# MoteinoR5USB.net
KiCad netlist of a schematic drawn in EAGLE
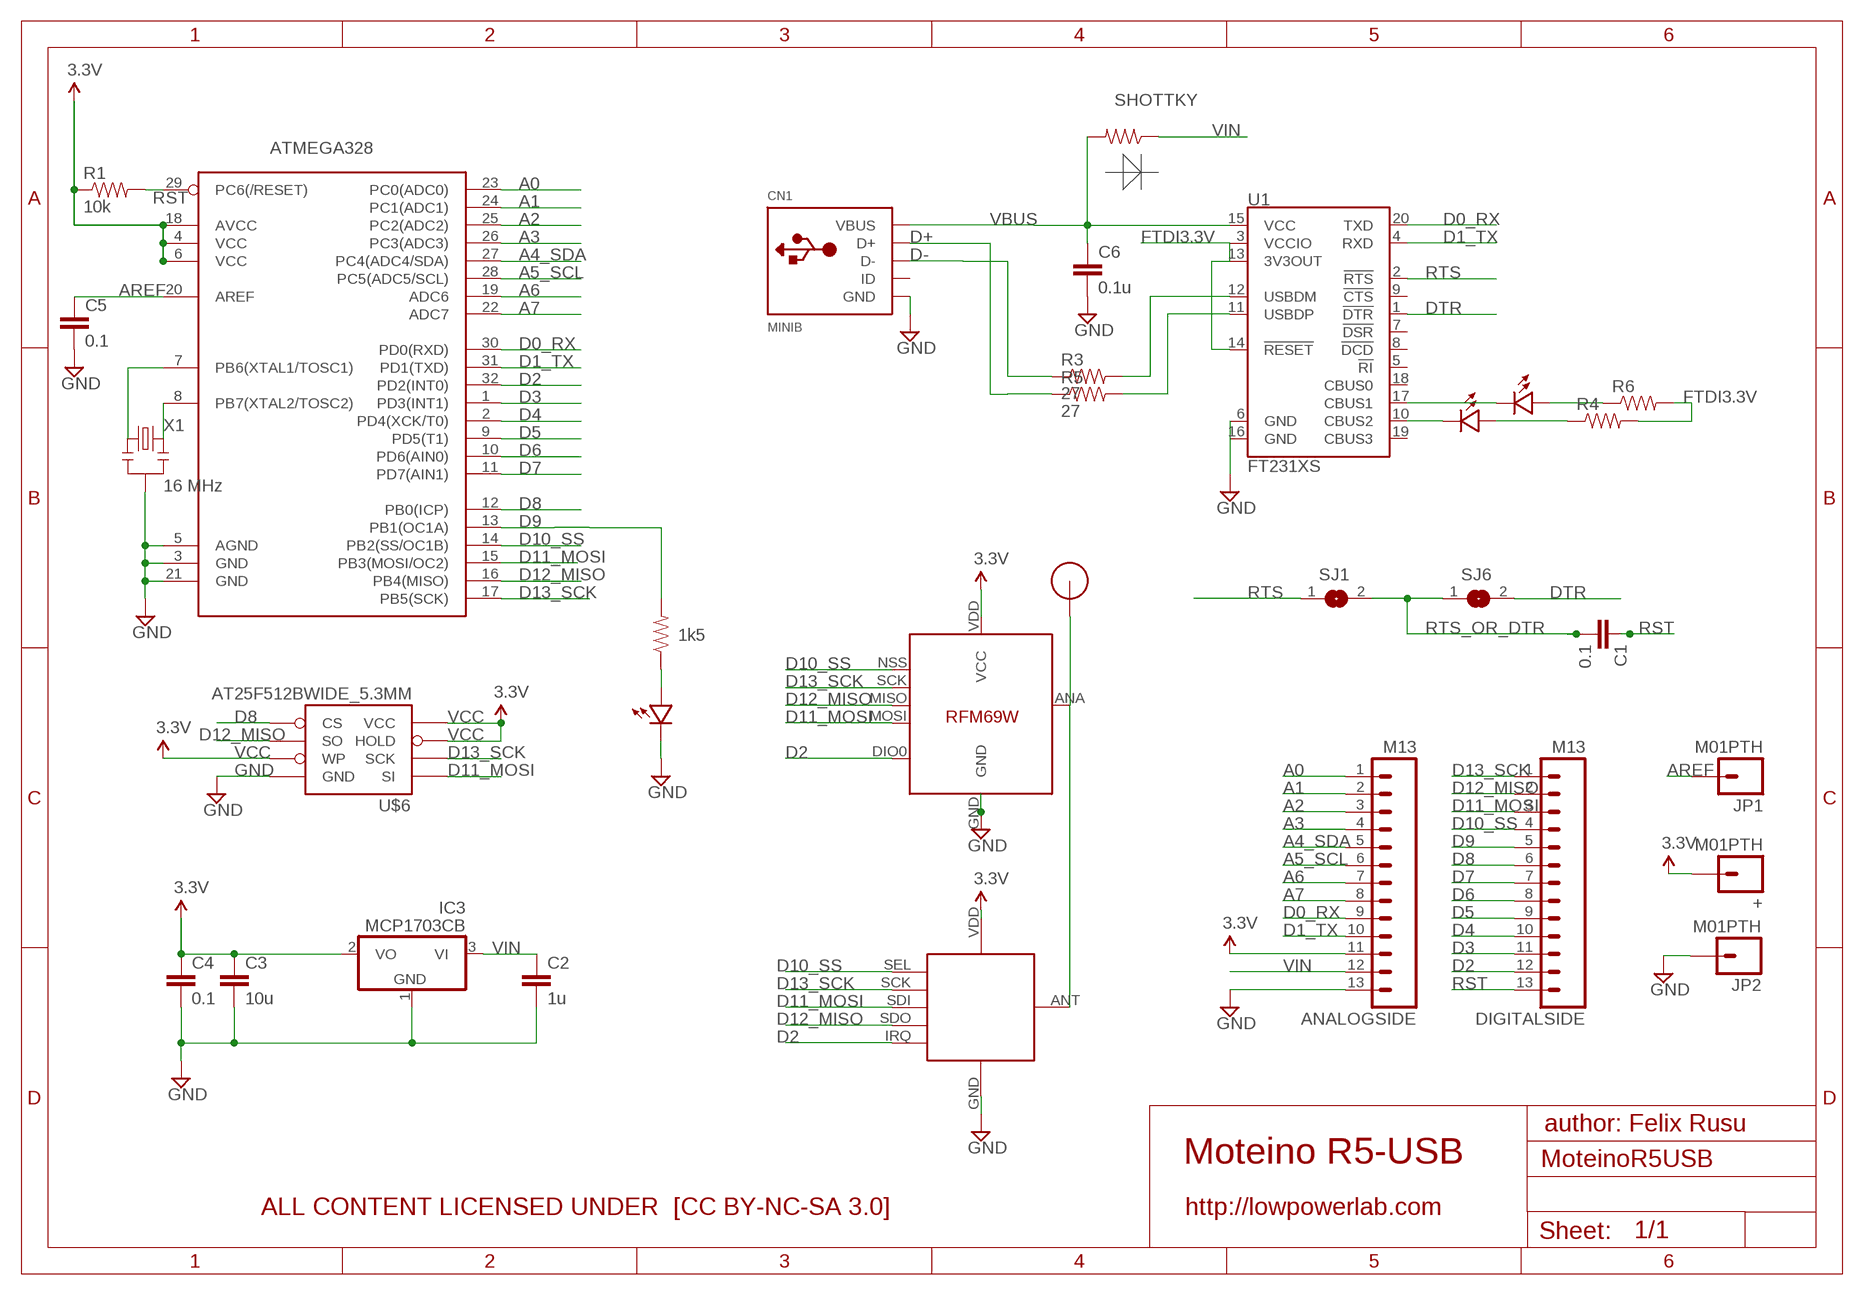
[diagram p0: schematic, sheet 1]

(export (version "E")
  (design (tool "Eeschema 10.0.6"))
  (components
    (comp (ref "+")
      (value "M01PTH")
      (footprint "eagle-import:1X01")
      (libsource (lib "eagle-import") (part "M01PTH"))
    )
    (comp (ref "ANALOGSIDE")
      (value "M13")
      (footprint "eagle-import:1X13")
      (libsource (lib "eagle-import") (part "M13"))
    )
    (comp (ref "ATMEGA328")
      (value "ATMega-328")
      (footprint "eagle-import:TQFP32-08")
      (libsource (lib "eagle-import") (part "ATMEGA168/328TQFP32"))
    )
    (comp (ref "C1")
      (value "0.1")
      (footprint "eagle-import:0603-CAP")
      (libsource (lib "eagle-import") (part "CAP0603-CAP"))
    )
    (comp (ref "C2")
      (value "1u")
      (footprint "eagle-import:0603-CAP")
      (libsource (lib "eagle-import") (part "CAP0603-CAP"))
    )
    (comp (ref "C3")
      (value "10u")
      (footprint "eagle-import:0805-CAP")
      (libsource (lib "eagle-import") (part "CAP0805-CAP"))
    )
    (comp (ref "C4")
      (value "0.1")
      (footprint "eagle-import:0603-CAP")
      (libsource (lib "eagle-import") (part "CAP0603-CAP"))
    )
    (comp (ref "C5")
      (value "0.1")
      (footprint "eagle-import:0603-CAP")
      (libsource (lib "eagle-import") (part "CAP0603-CAP"))
    )
    (comp (ref "C6")
      (value "0.1u")
      (footprint "eagle-import:0603-CAP")
      (libsource (lib "eagle-import") (part "CAP0603-CAP"))
    )
    (comp (ref "CN1")
      (value "MINIB")
      (footprint "eagle-import:USB-MINIB")
      (libsource (lib "eagle-import") (part "USBMINIB"))
    )
    (comp (ref "D")
      (value "SHOTTKY")
      (footprint "eagle-import:0603-RES")
      (libsource (lib "eagle-import") (part "RESISTOR0603-RES"))
    )
    (comp (ref "DIGITALSIDE")
      (value "M13")
      (footprint "eagle-import:1X13")
      (libsource (lib "eagle-import") (part "M13"))
    )
    (comp (ref "IC3")
      (value "MCP1703CB")
      (footprint "eagle-import:SOT23")
      (libsource (lib "eagle-import") (part "MCP1703CB"))
    )
    (comp (ref "JP1")
      (value "M01PTH")
      (footprint "eagle-import:1X01")
      (libsource (lib "eagle-import") (part "M01PTH"))
    )
    (comp (ref "JP2")
      (value "M01PTH")
      (footprint "eagle-import:1X01")
      (libsource (lib "eagle-import") (part "M01PTH"))
    )
    (comp (ref "R1")
      (value "10k")
      (footprint "eagle-import:0603-RES")
      (libsource (lib "eagle-import") (part "RESISTOR0603-RES"))
    )
    (comp (ref "R2")
      (value "1k5")
      (footprint "eagle-import:0603-RES")
      (libsource (lib "eagle-import") (part "RESISTOR0603-RES"))
    )
    (comp (ref "R3")
      (value "27")
      (footprint "eagle-import:0603-RES")
      (libsource (lib "eagle-import") (part "RESISTOR0603-RES"))
    )
    (comp (ref "R4")
      (value "RESISTOR0603-RES")
      (footprint "eagle-import:0603-RES")
      (libsource (lib "eagle-import") (part "RESISTOR0603-RES"))
    )
    (comp (ref "R5")
      (value "27")
      (footprint "eagle-import:0603-RES")
      (libsource (lib "eagle-import") (part "RESISTOR0603-RES"))
    )
    (comp (ref "R6")
      (value "RESISTOR0603-RES")
      (footprint "eagle-import:0603-RES")
      (libsource (lib "eagle-import") (part "RESISTOR0603-RES"))
    )
    (comp (ref "RFM12B")
      (value "RFM12B_MINPADS")
      (footprint "eagle-import:RFM12B-MINPADS")
      (libsource (lib "eagle-import") (part "RFM12B_MINPADS"))
    )
    (comp (ref "SJ1")
      (value "JUMPER")
      (footprint "eagle-import:SJW")
      (libsource (lib "eagle-import") (part "JUMPER"))
    )
    (comp (ref "SJ6")
      (value "JUMPER")
      (footprint "eagle-import:SJW")
      (libsource (lib "eagle-import") (part "JUMPER"))
    )
    (comp (ref "U$1")
      (value "RFM12B_ANTENNA")
      (footprint "eagle-import:RFM12B-ANTENNA")
      (libsource (lib "eagle-import") (part "RFM12B_ANTENNA"))
    )
    (comp (ref "U$2")
      (value "LED0603")
      (footprint "eagle-import:0603-LED")
      (libsource (lib "eagle-import") (part "LED0603"))
    )
    (comp (ref "U$4")
      (value "LED0603")
      (footprint "eagle-import:0603-LED")
      (libsource (lib "eagle-import") (part "LED0603"))
    )
    (comp (ref "U$5")
      (value "RFM69")
      (footprint "eagle-import:RFM69W-MINPADS")
      (libsource (lib "eagle-import") (part "RFM69"))
    )
    (comp (ref "U$6")
      (value "AT25F512BWIDE_5.3MM")
      (footprint "eagle-import:SO08WIDE")
      (libsource (lib "eagle-import") (part "AT25F512BWIDE_5.3MM"))
    )
    (comp (ref "U$7")
      (value "LED0603")
      (footprint "eagle-import:0603-LED")
      (libsource (lib "eagle-import") (part "LED0603"))
    )
    (comp (ref "U1")
      (value "FT231XS")
      (footprint "eagle-import:SSOP20_L")
      (libsource (lib "eagle-import") (part "FT231XS"))
    )
    (comp (ref "X1")
      (value "16 MHz")
      (footprint "eagle-import:RESONATOR-SMD")
      (libsource (lib "eagle-import") (part "RESONATORSMD"))
    )
  )
  (nets
    (net (code "1") (name "/A0") (class "Default")
      (node (ref "ANALOGSIDE") (pin "1") (pinfunction "1_1") (pintype "passive"))
      (node (ref "ATMEGA328") (pin "23") (pinfunction "PC0(ADC0)_23") (pintype "bidirectional"))
    )
    (net (code "2") (name "/A1") (class "Default")
      (node (ref "ANALOGSIDE") (pin "2") (pinfunction "2_2") (pintype "passive"))
      (node (ref "ATMEGA328") (pin "24") (pinfunction "PC1(ADC1)_24") (pintype "bidirectional"))
    )
    (net (code "3") (name "/A2") (class "Default")
      (node (ref "ANALOGSIDE") (pin "3") (pinfunction "3_3") (pintype "passive"))
      (node (ref "ATMEGA328") (pin "25") (pinfunction "PC2(ADC2)_25") (pintype "bidirectional"))
    )
    (net (code "4") (name "/A3") (class "Default")
      (node (ref "ANALOGSIDE") (pin "4") (pinfunction "4_4") (pintype "passive"))
      (node (ref "ATMEGA328") (pin "26") (pinfunction "PC3(ADC3)_26") (pintype "bidirectional"))
    )
    (net (code "5") (name "/A4_SDA") (class "Default")
      (node (ref "ANALOGSIDE") (pin "5") (pinfunction "5_5") (pintype "passive"))
      (node (ref "ATMEGA328") (pin "27") (pinfunction "PC4(ADC4/SDA)_27") (pintype "bidirectional"))
    )
    (net (code "6") (name "/A5_SCL") (class "Default")
      (node (ref "ANALOGSIDE") (pin "6") (pinfunction "6_6") (pintype "passive"))
      (node (ref "ATMEGA328") (pin "28") (pinfunction "PC5(ADC5/SCL)_28") (pintype "bidirectional"))
    )
    (net (code "7") (name "/A6") (class "Default")
      (node (ref "ANALOGSIDE") (pin "7") (pinfunction "7_7") (pintype "passive"))
      (node (ref "ATMEGA328") (pin "19") (pinfunction "ADC6_19") (pintype "bidirectional"))
    )
    (net (code "8") (name "/A7") (class "Default")
      (node (ref "ANALOGSIDE") (pin "8") (pinfunction "8_8") (pintype "passive"))
      (node (ref "ATMEGA328") (pin "22") (pinfunction "ADC7_22") (pintype "bidirectional"))
    )
    (net (code "9") (name "/AREF") (class "Default")
      (node (ref "ATMEGA328") (pin "20") (pinfunction "AREF_20") (pintype "bidirectional"))
      (node (ref "C5") (pin "1") (pinfunction "1_1") (pintype "passive"))
      (node (ref "JP1") (pin "1") (pinfunction "1_1") (pintype "passive"))
    )
    (net (code "10") (name "/D+") (class "Default")
      (node (ref "CN1") (pin "D+") (pinfunction "D+_D+") (pintype "bidirectional"))
      (node (ref "R5") (pin "1") (pinfunction "1_1") (pintype "passive"))
    )
    (net (code "11") (name "/D-") (class "Default")
      (node (ref "CN1") (pin "D-") (pinfunction "D-_D-") (pintype "bidirectional"))
      (node (ref "R3") (pin "1") (pinfunction "1_1") (pintype "passive"))
    )
    (net (code "12") (name "/D0_RX") (class "Default")
      (node (ref "ANALOGSIDE") (pin "9") (pinfunction "9_9") (pintype "passive"))
      (node (ref "ATMEGA328") (pin "30") (pinfunction "PD0(RXD)_30") (pintype "bidirectional"))
      (node (ref "U1") (pin "20") (pinfunction "TXD_20") (pintype "bidirectional"))
    )
    (net (code "13") (name "/D1_TX") (class "Default")
      (node (ref "ANALOGSIDE") (pin "10") (pinfunction "10_10") (pintype "passive"))
      (node (ref "ATMEGA328") (pin "31") (pinfunction "PD1(TXD)_31") (pintype "bidirectional"))
      (node (ref "U1") (pin "4") (pinfunction "RXD_4") (pintype "bidirectional"))
    )
    (net (code "14") (name "/D2") (class "Default")
      (node (ref "ATMEGA328") (pin "32") (pinfunction "PD2(INT0)_32") (pintype "bidirectional"))
      (node (ref "DIGITALSIDE") (pin "12") (pinfunction "12_12") (pintype "passive"))
      (node (ref "RFM12B") (pin "IRQ") (pinfunction "IRQ_IRQ") (pintype "bidirectional"))
      (node (ref "U$5") (pin "DIO0") (pinfunction "DIO0_DIO0") (pintype "open_collector"))
    )
    (net (code "15") (name "/D3") (class "Default")
      (node (ref "ATMEGA328") (pin "1") (pinfunction "PD3(INT1)_1") (pintype "bidirectional"))
      (node (ref "DIGITALSIDE") (pin "11") (pinfunction "11_11") (pintype "passive"))
    )
    (net (code "16") (name "/D4") (class "Default")
      (node (ref "ATMEGA328") (pin "2") (pinfunction "PD4(XCK/T0)_2") (pintype "bidirectional"))
      (node (ref "DIGITALSIDE") (pin "10") (pinfunction "10_10") (pintype "passive"))
    )
    (net (code "17") (name "/D5") (class "Default")
      (node (ref "ATMEGA328") (pin "9") (pinfunction "PD5(T1)_9") (pintype "bidirectional"))
      (node (ref "DIGITALSIDE") (pin "9") (pinfunction "9_9") (pintype "passive"))
    )
    (net (code "18") (name "/D6") (class "Default")
      (node (ref "ATMEGA328") (pin "10") (pinfunction "PD6(AIN0)_10") (pintype "bidirectional"))
      (node (ref "DIGITALSIDE") (pin "8") (pinfunction "8_8") (pintype "passive"))
    )
    (net (code "19") (name "/D7") (class "Default")
      (node (ref "ATMEGA328") (pin "11") (pinfunction "PD7(AIN1)_11") (pintype "bidirectional"))
      (node (ref "DIGITALSIDE") (pin "7") (pinfunction "7_7") (pintype "passive"))
    )
    (net (code "20") (name "/D8") (class "Default")
      (node (ref "ATMEGA328") (pin "12") (pinfunction "PB0(ICP)_12") (pintype "bidirectional"))
      (node (ref "DIGITALSIDE") (pin "6") (pinfunction "6_6") (pintype "passive"))
      (node (ref "U$6") (pin "1") (pinfunction "CS_1") (pintype "bidirectional"))
    )
    (net (code "21") (name "/D9") (class "Default")
      (node (ref "ATMEGA328") (pin "13") (pinfunction "PB1(OC1A)_13") (pintype "bidirectional"))
      (node (ref "DIGITALSIDE") (pin "5") (pinfunction "5_5") (pintype "passive"))
      (node (ref "R2") (pin "2") (pinfunction "2_2") (pintype "passive"))
    )
    (net (code "22") (name "/D10_SS") (class "Default")
      (node (ref "ATMEGA328") (pin "14") (pinfunction "PB2(SS/OC1B)_14") (pintype "bidirectional"))
      (node (ref "DIGITALSIDE") (pin "4") (pinfunction "4_4") (pintype "passive"))
      (node (ref "RFM12B") (pin "SEL") (pinfunction "SEL_SEL") (pintype "bidirectional"))
      (node (ref "U$5") (pin "NSS") (pinfunction "SEL_NSS") (pintype "input"))
    )
    (net (code "23") (name "/D11_MOSI") (class "Default")
      (node (ref "ATMEGA328") (pin "15") (pinfunction "PB3(MOSI/OC2)_15") (pintype "bidirectional"))
      (node (ref "DIGITALSIDE") (pin "3") (pinfunction "3_3") (pintype "passive"))
      (node (ref "RFM12B") (pin "SDI") (pinfunction "SDI/MOSI_SDI") (pintype "bidirectional"))
      (node (ref "U$5") (pin "MOSI") (pinfunction "MOSI_MOSI") (pintype "output"))
      (node (ref "U$6") (pin "5") (pinfunction "SI_5") (pintype "bidirectional"))
    )
    (net (code "24") (name "/D12_MISO") (class "Default")
      (node (ref "ATMEGA328") (pin "16") (pinfunction "PB4(MISO)_16") (pintype "bidirectional"))
      (node (ref "DIGITALSIDE") (pin "2") (pinfunction "2_2") (pintype "passive"))
      (node (ref "RFM12B") (pin "SDO") (pinfunction "SDO/MISO_SDO") (pintype "bidirectional"))
      (node (ref "U$5") (pin "MISO") (pinfunction "MISO_MISO") (pintype "input"))
      (node (ref "U$6") (pin "2") (pinfunction "SO_2") (pintype "bidirectional"))
    )
    (net (code "25") (name "/D13_SCK") (class "Default")
      (node (ref "ATMEGA328") (pin "17") (pinfunction "PB5(SCK)_17") (pintype "bidirectional"))
      (node (ref "DIGITALSIDE") (pin "1") (pinfunction "1_1") (pintype "passive"))
      (node (ref "RFM12B") (pin "SCK") (pinfunction "SCK_SCK") (pintype "bidirectional"))
      (node (ref "U$5") (pin "SCK") (pinfunction "SCK_SCK") (pintype "input"))
      (node (ref "U$6") (pin "6") (pinfunction "SCK_6") (pintype "bidirectional"))
    )
    (net (code "26") (name "/DTR") (class "Default")
      (node (ref "SJ6") (pin "2") (pinfunction "2_2") (pintype "passive"))
      (node (ref "U1") (pin "1") (pinfunction "~{DTR}_1") (pintype "bidirectional"))
    )
    (net (code "27") (name "/FTDI3.3V") (class "Default")
      (node (ref "R4") (pin "2") (pinfunction "2_2") (pintype "passive"))
      (node (ref "R6") (pin "2") (pinfunction "2_2") (pintype "passive"))
      (node (ref "U1") (pin "13") (pinfunction "3V3OUT_13") (pintype "bidirectional"))
      (node (ref "U1") (pin "14") (pinfunction "~{RESET}_14") (pintype "bidirectional"))
      (node (ref "U1") (pin "3") (pinfunction "VCCIO_3") (pintype "bidirectional"))
    )
    (net (code "28") (name "/RST") (class "Default")
      (node (ref "ATMEGA328") (pin "29") (pinfunction "PC6(/RESET)_29") (pintype "bidirectional"))
      (node (ref "C1") (pin "1") (pinfunction "1_1") (pintype "passive"))
      (node (ref "DIGITALSIDE") (pin "13") (pinfunction "13_13") (pintype "passive"))
      (node (ref "R1") (pin "2") (pinfunction "2_2") (pintype "passive"))
    )
    (net (code "29") (name "/RTS") (class "Default")
      (node (ref "SJ1") (pin "1") (pinfunction "1_1") (pintype "passive"))
      (node (ref "U1") (pin "2") (pinfunction "~{RTS}_2") (pintype "bidirectional"))
    )
    (net (code "30") (name "/RTS_OR_DTR") (class "Default")
      (node (ref "C1") (pin "2") (pinfunction "2_2") (pintype "passive"))
      (node (ref "SJ1") (pin "2") (pinfunction "2_2") (pintype "passive"))
      (node (ref "SJ6") (pin "1") (pinfunction "1_1") (pintype "passive"))
    )
    (net (code "31") (name "/VBUS") (class "Default")
      (node (ref "C6") (pin "1") (pinfunction "1_1") (pintype "passive"))
      (node (ref "CN1") (pin "VBUS") (pinfunction "VBUS_VBUS") (pintype "power_in"))
      (node (ref "D") (pin "2") (pinfunction "2_2") (pintype "passive"))
      (node (ref "U1") (pin "15") (pinfunction "VCC_15") (pintype "bidirectional"))
    )
    (net (code "32") (name "/VIN") (class "Default")
      (node (ref "ANALOGSIDE") (pin "12") (pinfunction "12_12") (pintype "passive"))
      (node (ref "C2") (pin "1") (pinfunction "1_1") (pintype "passive"))
      (node (ref "D") (pin "1") (pinfunction "1_1") (pintype "passive"))
      (node (ref "IC3") (pin "3") (pinfunction "VI_3") (pintype "input"))
    )
    (net (code "33") (name "3.3V") (class "Default")
      (node (ref "+") (pin "1") (pinfunction "1_1") (pintype "passive"))
      (node (ref "ANALOGSIDE") (pin "11") (pinfunction "11_11") (pintype "passive"))
      (node (ref "ATMEGA328") (pin "18") (pinfunction "AVCC_18") (pintype "bidirectional"))
      (node (ref "ATMEGA328") (pin "4") (pinfunction "VCC_4") (pintype "bidirectional"))
      (node (ref "ATMEGA328") (pin "6") (pinfunction "VCC_6") (pintype "bidirectional"))
      (node (ref "C3") (pin "1") (pinfunction "1_1") (pintype "passive"))
      (node (ref "C4") (pin "1") (pinfunction "1_1") (pintype "passive"))
      (node (ref "IC3") (pin "2") (pinfunction "VO_2") (pintype "passive"))
      (node (ref "R1") (pin "1") (pinfunction "1_1") (pintype "passive"))
      (node (ref "RFM12B") (pin "VDD") (pinfunction "VDD_VDD") (pintype "bidirectional"))
      (node (ref "U$5") (pin "VDD") (pinfunction "VCC_VDD") (pintype "power_in"))
      (node (ref "U$6") (pin "3") (pinfunction "WP_3") (pintype "bidirectional"))
      (node (ref "U$6") (pin "7") (pinfunction "HOLD_7") (pintype "bidirectional"))
      (node (ref "U$6") (pin "8") (pinfunction "VCC_8") (pintype "bidirectional"))
    )
    (net (code "34") (name "GND") (class "Default")
      (node (ref "ANALOGSIDE") (pin "13") (pinfunction "13_13") (pintype "passive"))
      (node (ref "ATMEGA328") (pin "21") (pinfunction "GND_21") (pintype "bidirectional"))
      (node (ref "ATMEGA328") (pin "3") (pinfunction "GND_3") (pintype "bidirectional"))
      (node (ref "ATMEGA328") (pin "5") (pinfunction "AGND_5") (pintype "bidirectional"))
      (node (ref "C2") (pin "2") (pinfunction "2_2") (pintype "passive"))
      (node (ref "C3") (pin "2") (pinfunction "2_2") (pintype "passive"))
      (node (ref "C4") (pin "2") (pinfunction "2_2") (pintype "passive"))
      (node (ref "C5") (pin "2") (pinfunction "2_2") (pintype "passive"))
      (node (ref "C6") (pin "2") (pinfunction "2_2") (pintype "passive"))
      (node (ref "CN1") (pin "GND") (pinfunction "GND_GND") (pintype "power_in"))
      (node (ref "IC3") (pin "1") (pinfunction "GND_1") (pintype "passive"))
      (node (ref "JP2") (pin "1") (pinfunction "1_1") (pintype "passive"))
      (node (ref "RFM12B") (pin "GND") (pinfunction "GND_GND") (pintype "bidirectional"))
      (node (ref "U$2") (pin "MINUS") (pinfunction "MINUS_MINUS") (pintype "passive"))
      (node (ref "U$5") (pin "GND") (pinfunction "GND_GND") (pintype "power_in"))
      (node (ref "U$6") (pin "4") (pinfunction "GND_4") (pintype "bidirectional"))
      (node (ref "U1") (pin "16") (pinfunction "GND_16") (pintype "bidirectional"))
      (node (ref "U1") (pin "6") (pinfunction "GND_6") (pintype "bidirectional"))
      (node (ref "X1") (pin "2") (pinfunction "2_2") (pintype "passive"))
    )
    (net (code "35") (name "Net-(ATMEGA328-PB6(XTAL1{slash}TOSC1))") (class "Default")
      (node (ref "ATMEGA328") (pin "7") (pinfunction "PB6(XTAL1/TOSC1)_7") (pintype "bidirectional"))
      (node (ref "X1") (pin "1") (pinfunction "1_1") (pintype "passive"))
    )
    (net (code "36") (name "Net-(ATMEGA328-PB7(XTAL2{slash}TOSC2))") (class "Default")
      (node (ref "ATMEGA328") (pin "8") (pinfunction "PB7(XTAL2/TOSC2)_8") (pintype "bidirectional"))
      (node (ref "X1") (pin "3") (pinfunction "3_3") (pintype "passive"))
    )
    (net (code "37") (name "Net-(R2-Pad1)") (class "Default")
      (node (ref "R2") (pin "1") (pinfunction "1_1") (pintype "passive"))
      (node (ref "U$2") (pin "PLUS") (pinfunction "PLUS_PLUS") (pintype "passive"))
    )
    (net (code "38") (name "Net-(R4-Pad1)") (class "Default")
      (node (ref "R4") (pin "1") (pinfunction "1_1") (pintype "passive"))
      (node (ref "U$7") (pin "PLUS") (pinfunction "PLUS_PLUS") (pintype "passive"))
    )
    (net (code "39") (name "Net-(R6-Pad1)") (class "Default")
      (node (ref "R6") (pin "1") (pinfunction "1_1") (pintype "passive"))
      (node (ref "U$4") (pin "PLUS") (pinfunction "PLUS_PLUS") (pintype "passive"))
    )
    (net (code "40") (name "Net-(U$1-1)") (class "Default")
      (node (ref "RFM12B") (pin "ANT") (pinfunction "ANT_ANT") (pintype "bidirectional"))
      (node (ref "U$1") (pin "P$1") (pinfunction "1_P$1") (pintype "bidirectional"))
      (node (ref "U$5") (pin "ANA") (pinfunction "ANT_ANA") (pintype "passive"))
    )
    (net (code "41") (name "Net-(U1-CBUS1)") (class "Default")
      (node (ref "U$4") (pin "MINUS") (pinfunction "MINUS_MINUS") (pintype "passive"))
      (node (ref "U1") (pin "17") (pinfunction "CBUS1_17") (pintype "bidirectional"))
    )
    (net (code "42") (name "Net-(U1-CBUS2)") (class "Default")
      (node (ref "U$7") (pin "MINUS") (pinfunction "MINUS_MINUS") (pintype "passive"))
      (node (ref "U1") (pin "10") (pinfunction "CBUS2_10") (pintype "bidirectional"))
    )
    (net (code "43") (name "Net-(U1-USBDM)") (class "Default")
      (node (ref "R3") (pin "2") (pinfunction "2_2") (pintype "passive"))
      (node (ref "U1") (pin "12") (pinfunction "USBDM_12") (pintype "bidirectional"))
    )
    (net (code "44") (name "Net-(U1-USBDP)") (class "Default")
      (node (ref "R5") (pin "2") (pinfunction "2_2") (pintype "passive"))
      (node (ref "U1") (pin "11") (pinfunction "USBDP_11") (pintype "bidirectional"))
    )
    (net (code "45") (name "unconnected-(CN1-PadID)") (class "Default")
      (node (ref "CN1") (pin "ID") (pinfunction "ID_ID") (pintype "bidirectional"))
    )
    (net (code "46") (name "unconnected-(U1-CBUS0-Pad18)") (class "Default")
      (node (ref "U1") (pin "18") (pinfunction "CBUS0_18") (pintype "bidirectional"))
    )
    (net (code "47") (name "unconnected-(U1-CBUS3-Pad19)") (class "Default")
      (node (ref "U1") (pin "19") (pinfunction "CBUS3_19") (pintype "bidirectional"))
    )
    (net (code "48") (name "unconnected-(U1-~{CTS}-Pad9)") (class "Default")
      (node (ref "U1") (pin "9") (pinfunction "~{CTS}_9") (pintype "bidirectional"))
    )
    (net (code "49") (name "unconnected-(U1-~{DCD}-Pad8)") (class "Default")
      (node (ref "U1") (pin "8") (pinfunction "~{DCD}_8") (pintype "bidirectional"))
    )
    (net (code "50") (name "unconnected-(U1-~{DSR}-Pad7)") (class "Default")
      (node (ref "U1") (pin "7") (pinfunction "~{DSR}_7") (pintype "bidirectional"))
    )
    (net (code "51") (name "unconnected-(U1-~{RI}-Pad5)") (class "Default")
      (node (ref "U1") (pin "5") (pinfunction "~{RI}_5") (pintype "bidirectional"))
    )
  )
)
